# disp.net
KiCad netlist of a schematic drawn in EAGLE
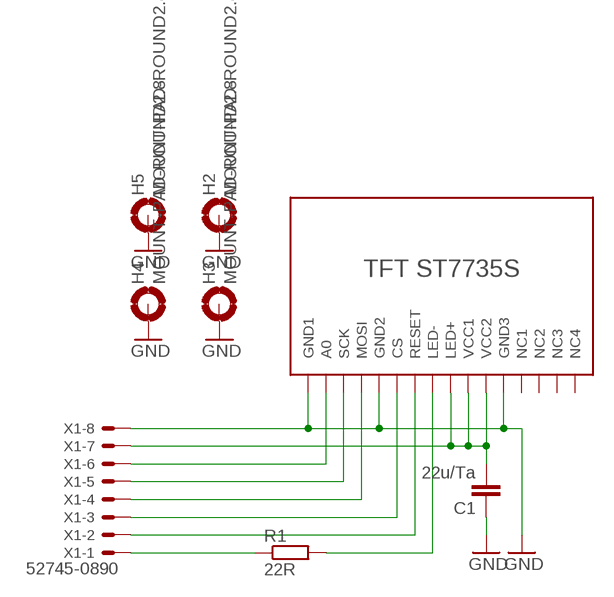
[diagram p0: schematic, sheet 1]

(export (version "E")
  (design (tool "Eeschema 10.0.6"))
  (components
    (comp (ref "C1")
      (value "22u/Ta")
      (footprint "eagle-import:C1206")
      (libsource (lib "eagle-import") (part "C-EUC1206"))
    )
    (comp (ref "H2")
      (value "MOUNT-PAD-ROUND2.8")
      (footprint "eagle-import:2,8-PAD")
      (libsource (lib "eagle-import") (part "MOUNT-PAD-ROUND2.8"))
    )
    (comp (ref "H3")
      (value "MOUNT-PAD-ROUND2.8")
      (footprint "eagle-import:2,8-PAD")
      (libsource (lib "eagle-import") (part "MOUNT-PAD-ROUND2.8"))
    )
    (comp (ref "H4")
      (value "MOUNT-PAD-ROUND2.8")
      (footprint "eagle-import:2,8-PAD")
      (libsource (lib "eagle-import") (part "MOUNT-PAD-ROUND2.8"))
    )
    (comp (ref "H5")
      (value "MOUNT-PAD-ROUND2.8")
      (footprint "eagle-import:2,8-PAD")
      (libsource (lib "eagle-import") (part "MOUNT-PAD-ROUND2.8"))
    )
    (comp (ref "R1")
      (value "22R")
      (footprint "eagle-import:R0805")
      (libsource (lib "eagle-import") (part "R-EU_R0805"))
    )
    (comp (ref "U$1")
      (value "TFT_ST7735S")
      (footprint "eagle-import:TFT_ST7735S")
      (libsource (lib "eagle-import") (part "TFT_ST7735S"))
    )
    (comp (ref "X1")
      (value "52745-0890")
      (footprint "eagle-import:52745-0890")
      (libsource (lib "eagle-import") (part "52745-0890"))
    )
  )
  (nets
    (net (code "1") (name "GND") (class "Default")
      (node (ref "C1") (pin "1") (pinfunction "1_1") (pintype "passive"))
      (node (ref "H2") (pin "B2,8") (pinfunction "MOUNT_B2,8") (pintype "passive"))
      (node (ref "H3") (pin "B2,8") (pinfunction "MOUNT_B2,8") (pintype "passive"))
      (node (ref "H4") (pin "B2,8") (pinfunction "MOUNT_B2,8") (pintype "passive"))
      (node (ref "H5") (pin "B2,8") (pinfunction "MOUNT_B2,8") (pintype "passive"))
      (node (ref "U$1") (pin "GND1") (pinfunction "GND1_GND1") (pintype "bidirectional"))
      (node (ref "U$1") (pin "GND2") (pinfunction "GND2_GND2") (pintype "bidirectional"))
      (node (ref "U$1") (pin "GND3") (pinfunction "GND3_GND3") (pintype "bidirectional"))
      (node (ref "X1") (pin "8") (pinfunction "S_8") (pintype "passive"))
    )
    (net (code "2") (name "Net-(R1-Pad2)") (class "Default")
      (node (ref "R1") (pin "2") (pinfunction "2_2") (pintype "passive"))
      (node (ref "U$1") (pin "LED-") (pinfunction "LED-_LED-") (pintype "bidirectional"))
    )
    (net (code "3") (name "Net-(X1A-S)") (class "Default")
      (node (ref "R1") (pin "1") (pinfunction "1_1") (pintype "passive"))
      (node (ref "X1") (pin "1") (pinfunction "S_1") (pintype "passive"))
    )
    (net (code "4") (name "Net-(X1B-S)") (class "Default")
      (node (ref "U$1") (pin "RESET") (pinfunction "RESET_RESET") (pintype "bidirectional"))
      (node (ref "X1") (pin "2") (pinfunction "S_2") (pintype "passive"))
    )
    (net (code "5") (name "Net-(X1C-S)") (class "Default")
      (node (ref "U$1") (pin "CS") (pinfunction "CS_CS") (pintype "bidirectional"))
      (node (ref "X1") (pin "3") (pinfunction "S_3") (pintype "passive"))
    )
    (net (code "6") (name "Net-(X1D-S)") (class "Default")
      (node (ref "U$1") (pin "MOSI") (pinfunction "MOSI_MOSI") (pintype "bidirectional"))
      (node (ref "X1") (pin "4") (pinfunction "S_4") (pintype "passive"))
    )
    (net (code "7") (name "Net-(X1E-S)") (class "Default")
      (node (ref "U$1") (pin "SCK") (pinfunction "SCK_SCK") (pintype "bidirectional"))
      (node (ref "X1") (pin "5") (pinfunction "S_5") (pintype "passive"))
    )
    (net (code "8") (name "Net-(X1F-S)") (class "Default")
      (node (ref "U$1") (pin "A0") (pinfunction "A0_A0") (pintype "bidirectional"))
      (node (ref "X1") (pin "6") (pinfunction "S_6") (pintype "passive"))
    )
    (net (code "9") (name "Net-(X1G-S)") (class "Default")
      (node (ref "C1") (pin "2") (pinfunction "2_2") (pintype "passive"))
      (node (ref "U$1") (pin "LED+") (pinfunction "LED+_LED+") (pintype "bidirectional"))
      (node (ref "U$1") (pin "VCC1") (pinfunction "VCC1_VCC1") (pintype "bidirectional"))
      (node (ref "U$1") (pin "VCC2") (pinfunction "VCC2_VCC2") (pintype "bidirectional"))
      (node (ref "X1") (pin "7") (pinfunction "S_7") (pintype "passive"))
    )
    (net (code "10") (name "unconnected-(U$1-PadNC1)") (class "Default")
      (node (ref "U$1") (pin "NC1") (pinfunction "NC1_NC1") (pintype "bidirectional"))
    )
    (net (code "11") (name "unconnected-(U$1-PadNC2)") (class "Default")
      (node (ref "U$1") (pin "NC2") (pinfunction "NC2_NC2") (pintype "bidirectional"))
    )
    (net (code "12") (name "unconnected-(U$1-PadNC3)") (class "Default")
      (node (ref "U$1") (pin "NC3") (pinfunction "NC3_NC3") (pintype "bidirectional"))
    )
    (net (code "13") (name "unconnected-(U$1-PadNC4)") (class "Default")
      (node (ref "U$1") (pin "NC4") (pinfunction "NC4_NC4") (pintype "bidirectional"))
    )
  )
)
